# repeater_v2.net
KiCad netlist of a schematic drawn in EasyEDA Pro
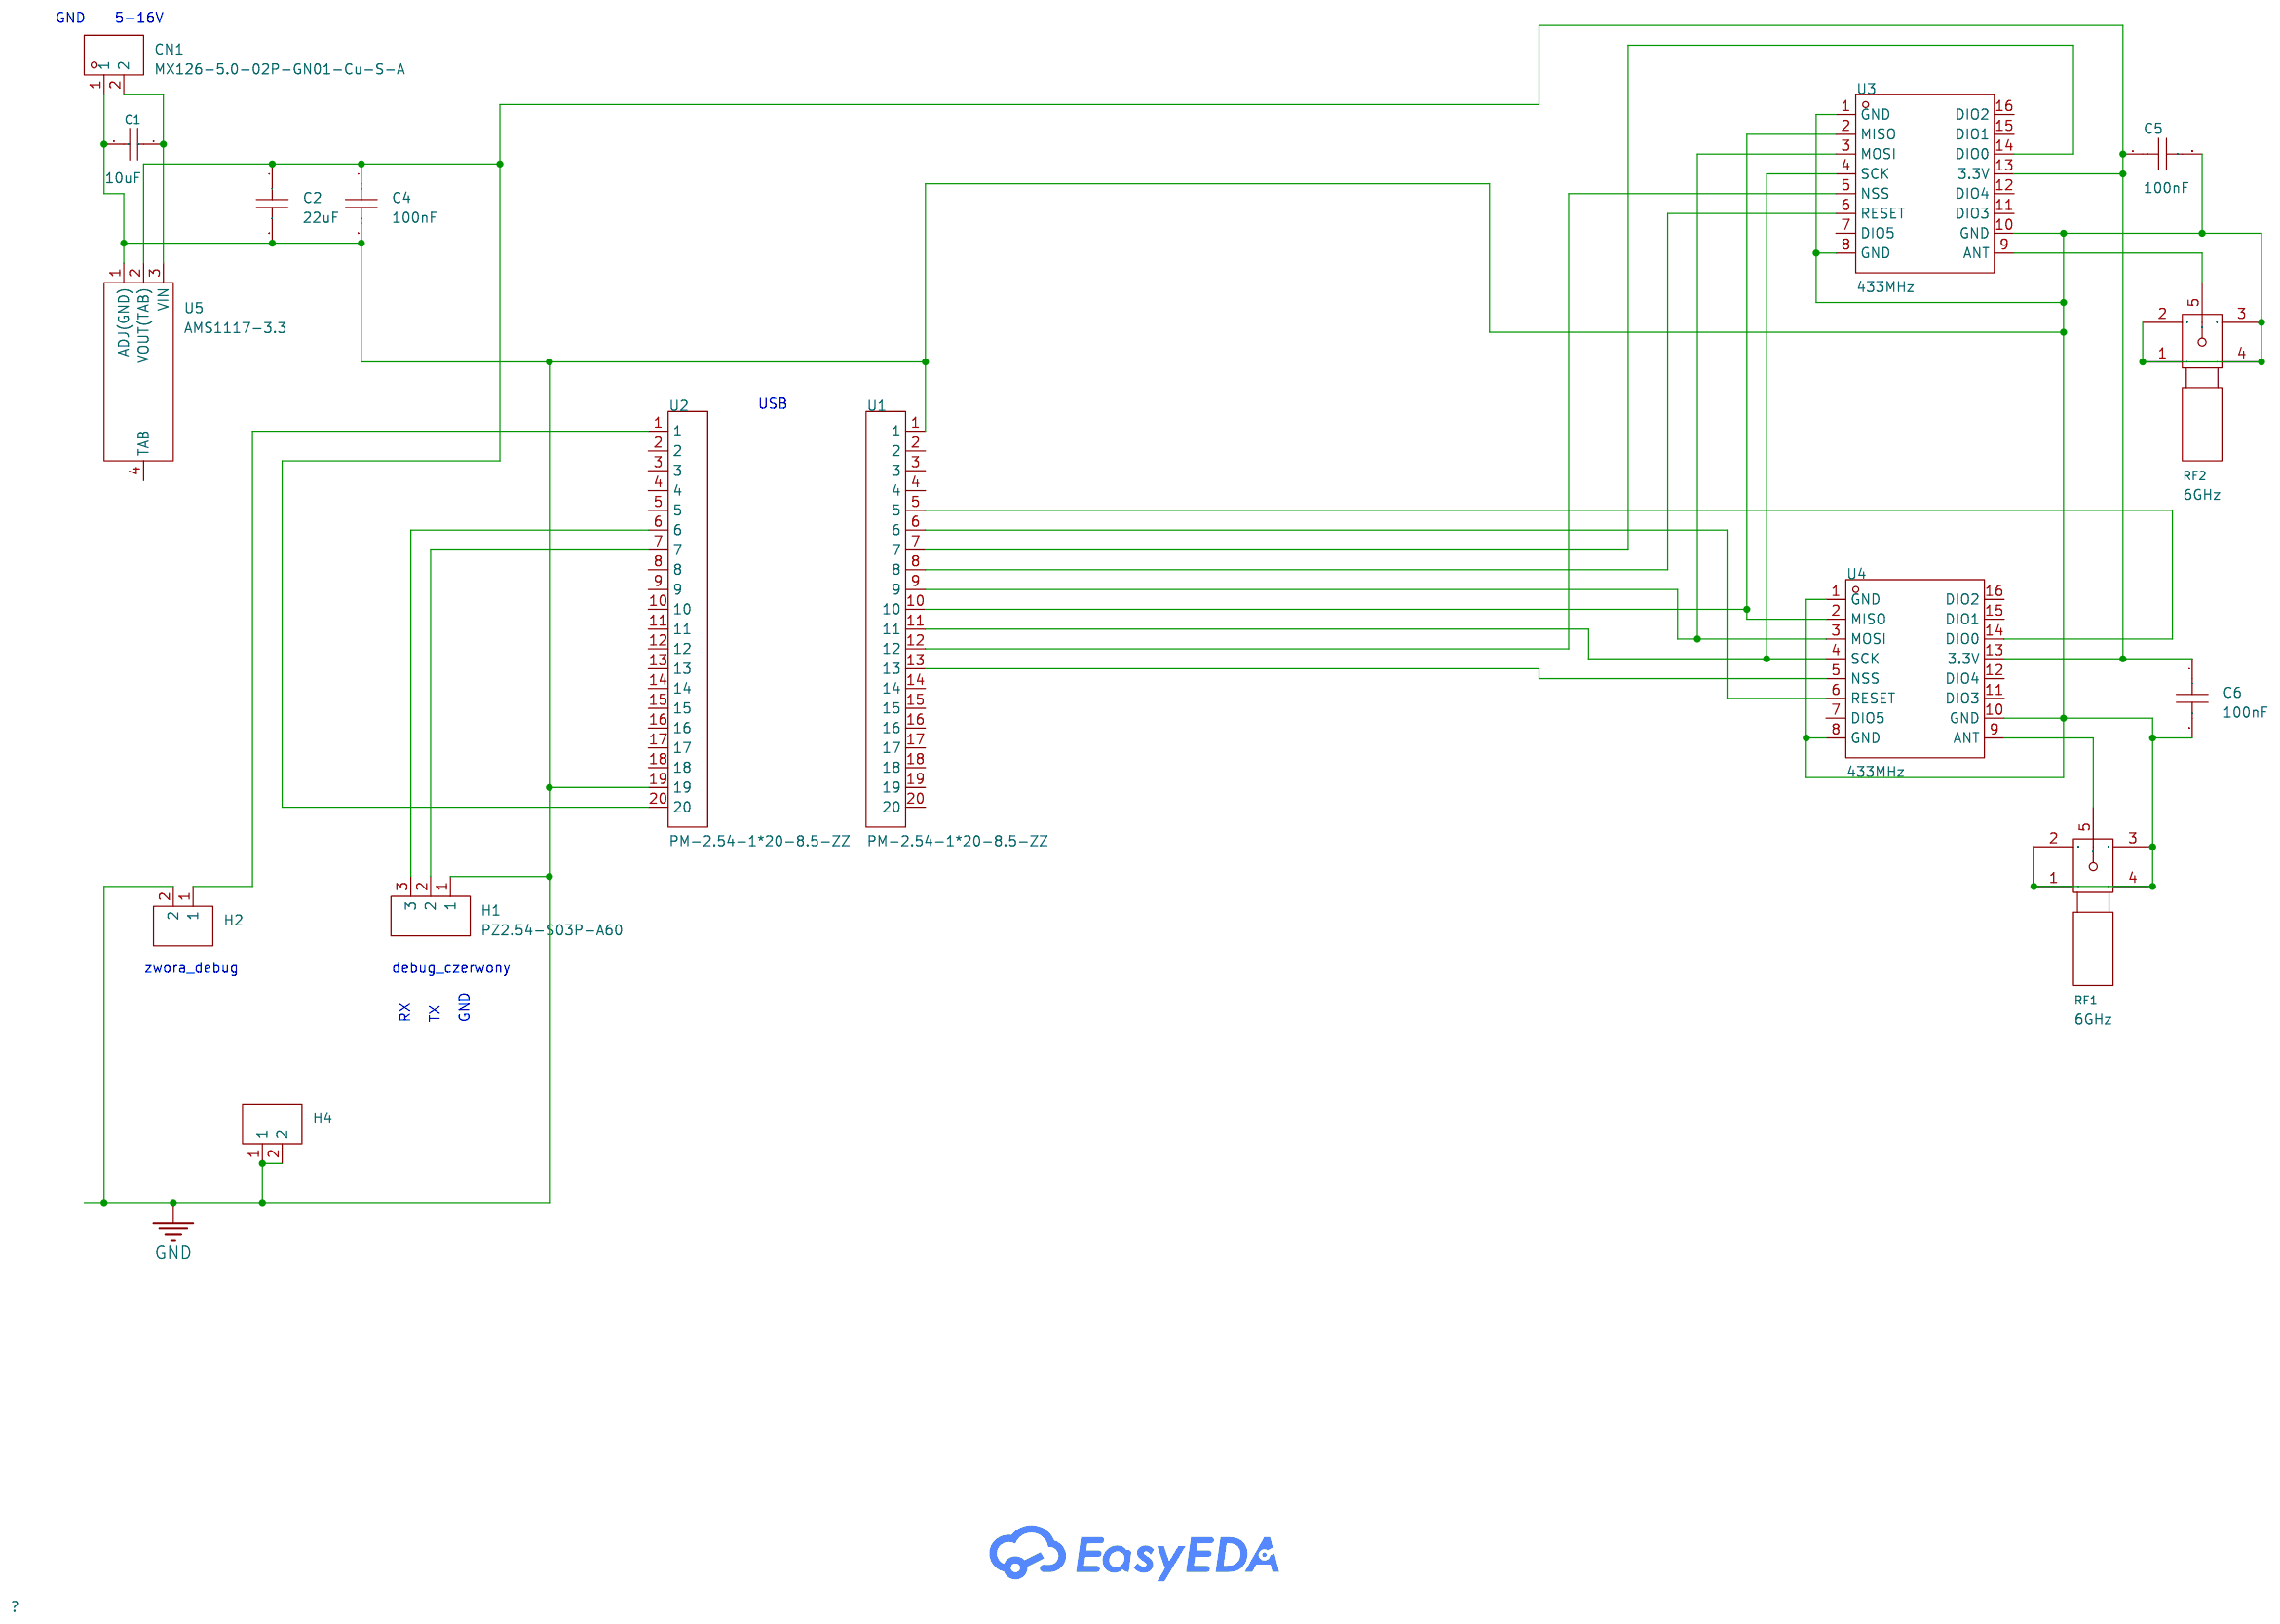
[diagram p0: schematic sheet]

(export (version "E")
  (design (tool "Eeschema 10.0.6"))
  (components
    (comp (ref "C1")
      (value "10uF")
      (footprint "easyedapro:C0603")
      (description "Capacitance:10uF Tolerance:±20% Tolerance:±20% Voltage Rating:16V Temperature Coefficient:X5R")
      (fields
        (field (name "Manufacturer Part") "CL10A106MO8NQNC")
        (field (name "Manufacturer") "SAMSUNG(三星)")
      )
      (libsource (lib "easyedapro") (part "CL10A106MO8NQNC"))
    )
    (comp (ref "C2")
      (value "22uF")
      (footprint "easyedapro:C0603")
      (description "Capacitance:22uF Tolerance:±20% Tolerance:±20% Voltage Rating:6.3V Temperature Coefficient:X5R")
      (fields
        (field (name "Manufacturer Part") "CL10A226MQ8NRNC")
        (field (name "Manufacturer") "SAMSUNG(三星)")
      )
      (libsource (lib "easyedapro") (part "CL10A226MQ8NRNC"))
    )
    (comp (ref "C4")
      (value "100nF")
      (footprint "easyedapro:C0603")
      (description "Capacitance:100nF Tolerance:±10% Tolerance:±10% Voltage Rating:50V Temperature Coefficient:X7R")
      (fields
        (field (name "Manufacturer Part") "CC0603KRX7R9BB104")
        (field (name "Manufacturer") "YAGEO(国巨)")
      )
      (libsource (lib "easyedapro") (part "CAP"))
    )
    (comp (ref "C5")
      (value "100nF")
      (footprint "easyedapro:C0603")
      (description "Capacitance:100nF Tolerance:±10% Tolerance:±10% Voltage Rating:50V Temperature Coefficient:X7R")
      (fields
        (field (name "Manufacturer Part") "CC0603KRX7R9BB104")
        (field (name "Manufacturer") "YAGEO(国巨)")
      )
      (libsource (lib "easyedapro") (part "CAP"))
    )
    (comp (ref "C6")
      (value "100nF")
      (footprint "easyedapro:C0603")
      (description "Capacitance:100nF Tolerance:±10% Tolerance:±10% Voltage Rating:50V Temperature Coefficient:X7R")
      (fields
        (field (name "Manufacturer Part") "CC0603KRX7R9BB104")
        (field (name "Manufacturer") "YAGEO(国巨)")
      )
      (libsource (lib "easyedapro") (part "CAP"))
    )
    (comp (ref "CN1")
      (value "MX126-5.0-02P-GN01-Cu-S-A")
      (footprint "easyedapro:CONN-TH_2P-P5.00_MX126-5.0-GN01-02P-CU-S-A")
      (fields (field (name "Manufacturer") "MAX(迈旭)"))
      (libsource (lib "easyedapro") (part "MX126-5.0-GN01-02P-CU-S-A"))
    )
    (comp (ref "H1")
      (value "PZ2.54-S03P-A60")
      (footprint "easyedapro:HDR-TH_3P-P2.54-V-M-B")
      (fields (field (name "Manufacturer") "JXTCONN(聚兴泰)"))
      (libsource (lib "easyedapro") (part "PZ2.54-S03P-A60"))
    )
    (comp (ref "H2")
      (value "PZ2.54-0102P-H25")
      (footprint "easyedapro:HDR-TH_2P-P2.54-V-M_2")
      (fields (field (name "Manufacturer") "JXTCONN(聚兴泰)"))
      (libsource (lib "easyedapro") (part "PZ2.54-0102P-H25"))
    )
    (comp (ref "H4")
      (value "PZ2.54-0102P-H25")
      (footprint "easyedapro:HDR-TH_2P-P2.54-V-M_2")
      (fields (field (name "Manufacturer") "JXTCONN(聚兴泰)"))
      (libsource (lib "easyedapro") (part "PZ2.54-0102P-H25"))
    )
    (comp (ref "RF1")
      (value "6GHz")
      (footprint "easyedapro:SMA-TH_BWSMA-KE-Z001")
      (fields
        (field (name "Manufacturer Part") "BWSMA-KE-Z001")
        (field (name "Manufacturer") "BAT WIRELESS(蝙蝠无线)")
      )
      (libsource (lib "easyedapro") (part "BWSMA-KE-Z001"))
    )
    (comp (ref "RF2")
      (value "6GHz")
      (footprint "easyedapro:SMA-TH_BWSMA-KE-Z001")
      (fields
        (field (name "Manufacturer Part") "BWSMA-KE-Z001")
        (field (name "Manufacturer") "BAT WIRELESS(蝙蝠无线)")
      )
      (libsource (lib "easyedapro") (part "BWSMA-KE-Z001"))
    )
    (comp (ref "U1")
      (value "PM-2.54-1*20-8.5-ZZ")
      (footprint "easyedapro:HDR-TH_20P-P2.54-V-F-2")
      (fields (field (name "Manufacturer") "BXCONN(宝讯)"))
      (libsource (lib "easyedapro") (part "PM-2.54-1*20-8.5-ZZ"))
    )
    (comp (ref "U2")
      (value "PM-2.54-1*20-8.5-ZZ")
      (footprint "easyedapro:HDR-TH_20P-P2.54-V-F-2")
      (fields (field (name "Manufacturer") "BXCONN(宝讯)"))
      (libsource (lib "easyedapro") (part "PM-2.54-1*20-8.5-ZZ"))
    )
    (comp (ref "U3")
      (value "433MHz")
      (footprint "easyedapro:COMM-SMD_RFM95W")
      (fields
        (field (name "Manufacturer Part") "DL-RFM96-433M")
        (field (name "Manufacturer") "DreamLNK(骏晔科技)")
      )
      (libsource (lib "easyedapro") (part "DL-RFM96-433M"))
    )
    (comp (ref "U4")
      (value "433MHz")
      (footprint "easyedapro:COMM-SMD_RFM95W")
      (fields
        (field (name "Manufacturer Part") "DL-RFM96-433M")
        (field (name "Manufacturer") "DreamLNK(骏晔科技)")
      )
      (libsource (lib "easyedapro") (part "DL-RFM96-433M"))
    )
    (comp (ref "U5")
      (value "AMS1117-3.3")
      (footprint "easyedapro:SOT-223-4_L6.5-W3.5-P2.30-LS7.0-BR")
      (fields (field (name "Manufacturer") "UMW(友台半导体)"))
      (libsource (lib "easyedapro") (part "AMS1117-3.3_C347222"))
    )
  )
  (nets
    (net (code "1") (name "GND") (class "Default")
      (node (ref "C1") (pin "1") (pinfunction "1_1") (pintype "input"))
      (node (ref "C2") (pin "2") (pinfunction "2_2") (pintype "unspecified"))
      (node (ref "C4") (pin "2") (pinfunction "2_2") (pintype "input"))
      (node (ref "C5") (pin "2") (pinfunction "2_2") (pintype "input"))
      (node (ref "C6") (pin "2") (pinfunction "2_2") (pintype "input"))
      (node (ref "CN1") (pin "1") (pinfunction "1_1") (pintype "unspecified"))
      (node (ref "H1") (pin "1") (pinfunction "1_1") (pintype "unspecified"))
      (node (ref "H2") (pin "2") (pinfunction "2_2") (pintype "unspecified"))
      (node (ref "H4") (pin "1") (pinfunction "1_1") (pintype "unspecified"))
      (node (ref "H4") (pin "2") (pinfunction "2_2") (pintype "unspecified"))
      (node (ref "RF1") (pin "1") (pinfunction "1_1") (pintype "input"))
      (node (ref "RF1") (pin "2") (pinfunction "2_2") (pintype "input"))
      (node (ref "RF1") (pin "3") (pinfunction "3_3") (pintype "input"))
      (node (ref "RF1") (pin "4") (pinfunction "4_4") (pintype "input"))
      (node (ref "RF2") (pin "1") (pinfunction "1_1") (pintype "input"))
      (node (ref "RF2") (pin "2") (pinfunction "2_2") (pintype "input"))
      (node (ref "RF2") (pin "3") (pinfunction "3_3") (pintype "input"))
      (node (ref "RF2") (pin "4") (pinfunction "4_4") (pintype "input"))
      (node (ref "U1") (pin "1") (pinfunction "1_1") (pintype "unspecified"))
      (node (ref "U2") (pin "19") (pinfunction "19_19") (pintype "unspecified"))
      (node (ref "U3") (pin "1") (pinfunction "GND_1") (pintype "unspecified"))
      (node (ref "U3") (pin "10") (pinfunction "GND_10") (pintype "unspecified"))
      (node (ref "U3") (pin "8") (pinfunction "GND_8") (pintype "unspecified"))
      (node (ref "U4") (pin "1") (pinfunction "GND_1") (pintype "unspecified"))
      (node (ref "U4") (pin "10") (pinfunction "GND_10") (pintype "unspecified"))
      (node (ref "U4") (pin "8") (pinfunction "GND_8") (pintype "unspecified"))
      (node (ref "U5") (pin "1") (pinfunction "ADJ(GND)_1") (pintype "unspecified"))
    )
    (net (code "2") (name "Net-(H1-Pad2)") (class "Default")
      (node (ref "H1") (pin "2") (pinfunction "2_2") (pintype "unspecified"))
      (node (ref "U2") (pin "7") (pinfunction "7_7") (pintype "unspecified"))
    )
    (net (code "3") (name "Net-(H1-Pad3)") (class "Default")
      (node (ref "H1") (pin "3") (pinfunction "3_3") (pintype "unspecified"))
      (node (ref "U2") (pin "6") (pinfunction "6_6") (pintype "unspecified"))
    )
    (net (code "4") (name "Net-(H2-Pad1)") (class "Default")
      (node (ref "H2") (pin "1") (pinfunction "1_1") (pintype "unspecified"))
      (node (ref "U2") (pin "1") (pinfunction "1_1") (pintype "unspecified"))
    )
    (net (code "5") (name "Net-(U3-3.3V)") (class "Default")
      (node (ref "C2") (pin "1") (pinfunction "1_1") (pintype "unspecified"))
      (node (ref "C4") (pin "1") (pinfunction "1_1") (pintype "input"))
      (node (ref "C5") (pin "1") (pinfunction "1_1") (pintype "input"))
      (node (ref "C6") (pin "1") (pinfunction "1_1") (pintype "input"))
      (node (ref "U2") (pin "20") (pinfunction "20_20") (pintype "unspecified"))
      (node (ref "U3") (pin "13") (pinfunction "3.3V_13") (pintype "unspecified"))
      (node (ref "U4") (pin "13") (pinfunction "3.3V_13") (pintype "unspecified"))
      (node (ref "U5") (pin "2") (pinfunction "VOUT(TAB)_2") (pintype "unspecified"))
    )
    (net (code "6") (name "Net-(U3-ANT)") (class "Default")
      (node (ref "RF2") (pin "5") (pinfunction "5_5") (pintype "input"))
      (node (ref "U3") (pin "9") (pinfunction "ANT_9") (pintype "unspecified"))
    )
    (net (code "7") (name "Net-(U3-DIO0)") (class "Default")
      (node (ref "U1") (pin "7") (pinfunction "7_7") (pintype "unspecified"))
      (node (ref "U3") (pin "14") (pinfunction "DIO0_14") (pintype "unspecified"))
    )
    (net (code "8") (name "Net-(U3-MISO)") (class "Default")
      (node (ref "U1") (pin "10") (pinfunction "10_10") (pintype "unspecified"))
      (node (ref "U3") (pin "2") (pinfunction "MISO_2") (pintype "unspecified"))
      (node (ref "U4") (pin "2") (pinfunction "MISO_2") (pintype "unspecified"))
    )
    (net (code "9") (name "Net-(U3-MOSI)") (class "Default")
      (node (ref "U1") (pin "9") (pinfunction "9_9") (pintype "unspecified"))
      (node (ref "U3") (pin "3") (pinfunction "MOSI_3") (pintype "unspecified"))
      (node (ref "U4") (pin "3") (pinfunction "MOSI_3") (pintype "unspecified"))
    )
    (net (code "10") (name "Net-(U3-NSS)") (class "Default")
      (node (ref "U1") (pin "12") (pinfunction "12_12") (pintype "unspecified"))
      (node (ref "U3") (pin "5") (pinfunction "NSS_5") (pintype "unspecified"))
    )
    (net (code "11") (name "Net-(U3-RESET)") (class "Default")
      (node (ref "U1") (pin "8") (pinfunction "8_8") (pintype "unspecified"))
      (node (ref "U3") (pin "6") (pinfunction "RESET_6") (pintype "unspecified"))
    )
    (net (code "12") (name "Net-(U3-SCK)") (class "Default")
      (node (ref "U1") (pin "11") (pinfunction "11_11") (pintype "unspecified"))
      (node (ref "U3") (pin "4") (pinfunction "SCK_4") (pintype "unspecified"))
      (node (ref "U4") (pin "4") (pinfunction "SCK_4") (pintype "unspecified"))
    )
    (net (code "13") (name "Net-(U4-ANT)") (class "Default")
      (node (ref "RF1") (pin "5") (pinfunction "5_5") (pintype "input"))
      (node (ref "U4") (pin "9") (pinfunction "ANT_9") (pintype "unspecified"))
    )
    (net (code "14") (name "Net-(U4-DIO0)") (class "Default")
      (node (ref "U1") (pin "5") (pinfunction "5_5") (pintype "unspecified"))
      (node (ref "U4") (pin "14") (pinfunction "DIO0_14") (pintype "unspecified"))
    )
    (net (code "15") (name "Net-(U4-NSS)") (class "Default")
      (node (ref "U1") (pin "13") (pinfunction "13_13") (pintype "unspecified"))
      (node (ref "U4") (pin "5") (pinfunction "NSS_5") (pintype "unspecified"))
    )
    (net (code "16") (name "Net-(U4-RESET)") (class "Default")
      (node (ref "U1") (pin "6") (pinfunction "6_6") (pintype "unspecified"))
      (node (ref "U4") (pin "6") (pinfunction "RESET_6") (pintype "unspecified"))
    )
    (net (code "17") (name "Net-(U5-VIN)") (class "Default")
      (node (ref "C1") (pin "2") (pinfunction "2_2") (pintype "input"))
      (node (ref "CN1") (pin "2") (pinfunction "2_2") (pintype "unspecified"))
      (node (ref "U5") (pin "3") (pinfunction "VIN_3") (pintype "unspecified"))
    )
    (net (code "18") (name "unconnected-(U1-Pad2)") (class "Default")
      (node (ref "U1") (pin "2") (pinfunction "2_2") (pintype "unspecified"))
    )
    (net (code "19") (name "unconnected-(U1-Pad3)") (class "Default")
      (node (ref "U1") (pin "3") (pinfunction "3_3") (pintype "unspecified"))
    )
    (net (code "20") (name "unconnected-(U1-Pad4)") (class "Default")
      (node (ref "U1") (pin "4") (pinfunction "4_4") (pintype "unspecified"))
    )
    (net (code "21") (name "unconnected-(U1-Pad14)") (class "Default")
      (node (ref "U1") (pin "14") (pinfunction "14_14") (pintype "unspecified"))
    )
    (net (code "22") (name "unconnected-(U1-Pad15)") (class "Default")
      (node (ref "U1") (pin "15") (pinfunction "15_15") (pintype "unspecified"))
    )
    (net (code "23") (name "unconnected-(U1-Pad16)") (class "Default")
      (node (ref "U1") (pin "16") (pinfunction "16_16") (pintype "unspecified"))
    )
    (net (code "24") (name "unconnected-(U1-Pad17)") (class "Default")
      (node (ref "U1") (pin "17") (pinfunction "17_17") (pintype "unspecified"))
    )
    (net (code "25") (name "unconnected-(U1-Pad18)") (class "Default")
      (node (ref "U1") (pin "18") (pinfunction "18_18") (pintype "unspecified"))
    )
    (net (code "26") (name "unconnected-(U1-Pad19)") (class "Default")
      (node (ref "U1") (pin "19") (pinfunction "19_19") (pintype "unspecified"))
    )
    (net (code "27") (name "unconnected-(U1-Pad20)") (class "Default")
      (node (ref "U1") (pin "20") (pinfunction "20_20") (pintype "unspecified"))
    )
    (net (code "28") (name "unconnected-(U2-Pad2)") (class "Default")
      (node (ref "U2") (pin "2") (pinfunction "2_2") (pintype "unspecified"))
    )
    (net (code "29") (name "unconnected-(U2-Pad3)") (class "Default")
      (node (ref "U2") (pin "3") (pinfunction "3_3") (pintype "unspecified"))
    )
    (net (code "30") (name "unconnected-(U2-Pad4)") (class "Default")
      (node (ref "U2") (pin "4") (pinfunction "4_4") (pintype "unspecified"))
    )
    (net (code "31") (name "unconnected-(U2-Pad5)") (class "Default")
      (node (ref "U2") (pin "5") (pinfunction "5_5") (pintype "unspecified"))
    )
    (net (code "32") (name "unconnected-(U2-Pad8)") (class "Default")
      (node (ref "U2") (pin "8") (pinfunction "8_8") (pintype "unspecified"))
    )
    (net (code "33") (name "unconnected-(U2-Pad9)") (class "Default")
      (node (ref "U2") (pin "9") (pinfunction "9_9") (pintype "unspecified"))
    )
    (net (code "34") (name "unconnected-(U2-Pad10)") (class "Default")
      (node (ref "U2") (pin "10") (pinfunction "10_10") (pintype "unspecified"))
    )
    (net (code "35") (name "unconnected-(U2-Pad11)") (class "Default")
      (node (ref "U2") (pin "11") (pinfunction "11_11") (pintype "unspecified"))
    )
    (net (code "36") (name "unconnected-(U2-Pad12)") (class "Default")
      (node (ref "U2") (pin "12") (pinfunction "12_12") (pintype "unspecified"))
    )
    (net (code "37") (name "unconnected-(U2-Pad13)") (class "Default")
      (node (ref "U2") (pin "13") (pinfunction "13_13") (pintype "unspecified"))
    )
    (net (code "38") (name "unconnected-(U2-Pad14)") (class "Default")
      (node (ref "U2") (pin "14") (pinfunction "14_14") (pintype "unspecified"))
    )
    (net (code "39") (name "unconnected-(U2-Pad15)") (class "Default")
      (node (ref "U2") (pin "15") (pinfunction "15_15") (pintype "unspecified"))
    )
    (net (code "40") (name "unconnected-(U2-Pad16)") (class "Default")
      (node (ref "U2") (pin "16") (pinfunction "16_16") (pintype "unspecified"))
    )
    (net (code "41") (name "unconnected-(U2-Pad17)") (class "Default")
      (node (ref "U2") (pin "17") (pinfunction "17_17") (pintype "unspecified"))
    )
    (net (code "42") (name "unconnected-(U2-Pad18)") (class "Default")
      (node (ref "U2") (pin "18") (pinfunction "18_18") (pintype "unspecified"))
    )
    (net (code "43") (name "unconnected-(U3-DIO1-Pad15)") (class "Default")
      (node (ref "U3") (pin "15") (pinfunction "DIO1_15") (pintype "unspecified"))
    )
    (net (code "44") (name "unconnected-(U3-DIO2-Pad16)") (class "Default")
      (node (ref "U3") (pin "16") (pinfunction "DIO2_16") (pintype "unspecified"))
    )
    (net (code "45") (name "unconnected-(U3-DIO3-Pad11)") (class "Default")
      (node (ref "U3") (pin "11") (pinfunction "DIO3_11") (pintype "unspecified"))
    )
    (net (code "46") (name "unconnected-(U3-DIO4-Pad12)") (class "Default")
      (node (ref "U3") (pin "12") (pinfunction "DIO4_12") (pintype "unspecified"))
    )
    (net (code "47") (name "unconnected-(U3-DIO5-Pad7)") (class "Default")
      (node (ref "U3") (pin "7") (pinfunction "DIO5_7") (pintype "unspecified"))
    )
    (net (code "48") (name "unconnected-(U4-DIO1-Pad15)") (class "Default")
      (node (ref "U4") (pin "15") (pinfunction "DIO1_15") (pintype "unspecified"))
    )
    (net (code "49") (name "unconnected-(U4-DIO2-Pad16)") (class "Default")
      (node (ref "U4") (pin "16") (pinfunction "DIO2_16") (pintype "unspecified"))
    )
    (net (code "50") (name "unconnected-(U4-DIO3-Pad11)") (class "Default")
      (node (ref "U4") (pin "11") (pinfunction "DIO3_11") (pintype "unspecified"))
    )
    (net (code "51") (name "unconnected-(U4-DIO4-Pad12)") (class "Default")
      (node (ref "U4") (pin "12") (pinfunction "DIO4_12") (pintype "unspecified"))
    )
    (net (code "52") (name "unconnected-(U4-DIO5-Pad7)") (class "Default")
      (node (ref "U4") (pin "7") (pinfunction "DIO5_7") (pintype "unspecified"))
    )
    (net (code "53") (name "unconnected-(U5-TAB-Pad4)") (class "Default")
      (node (ref "U5") (pin "4") (pinfunction "TAB_4") (pintype "unspecified"))
    )
  )
)
